# OSO-MISC-21-018_Temperature_Board.net
KiCad netlist of a schematic drawn in EAGLE
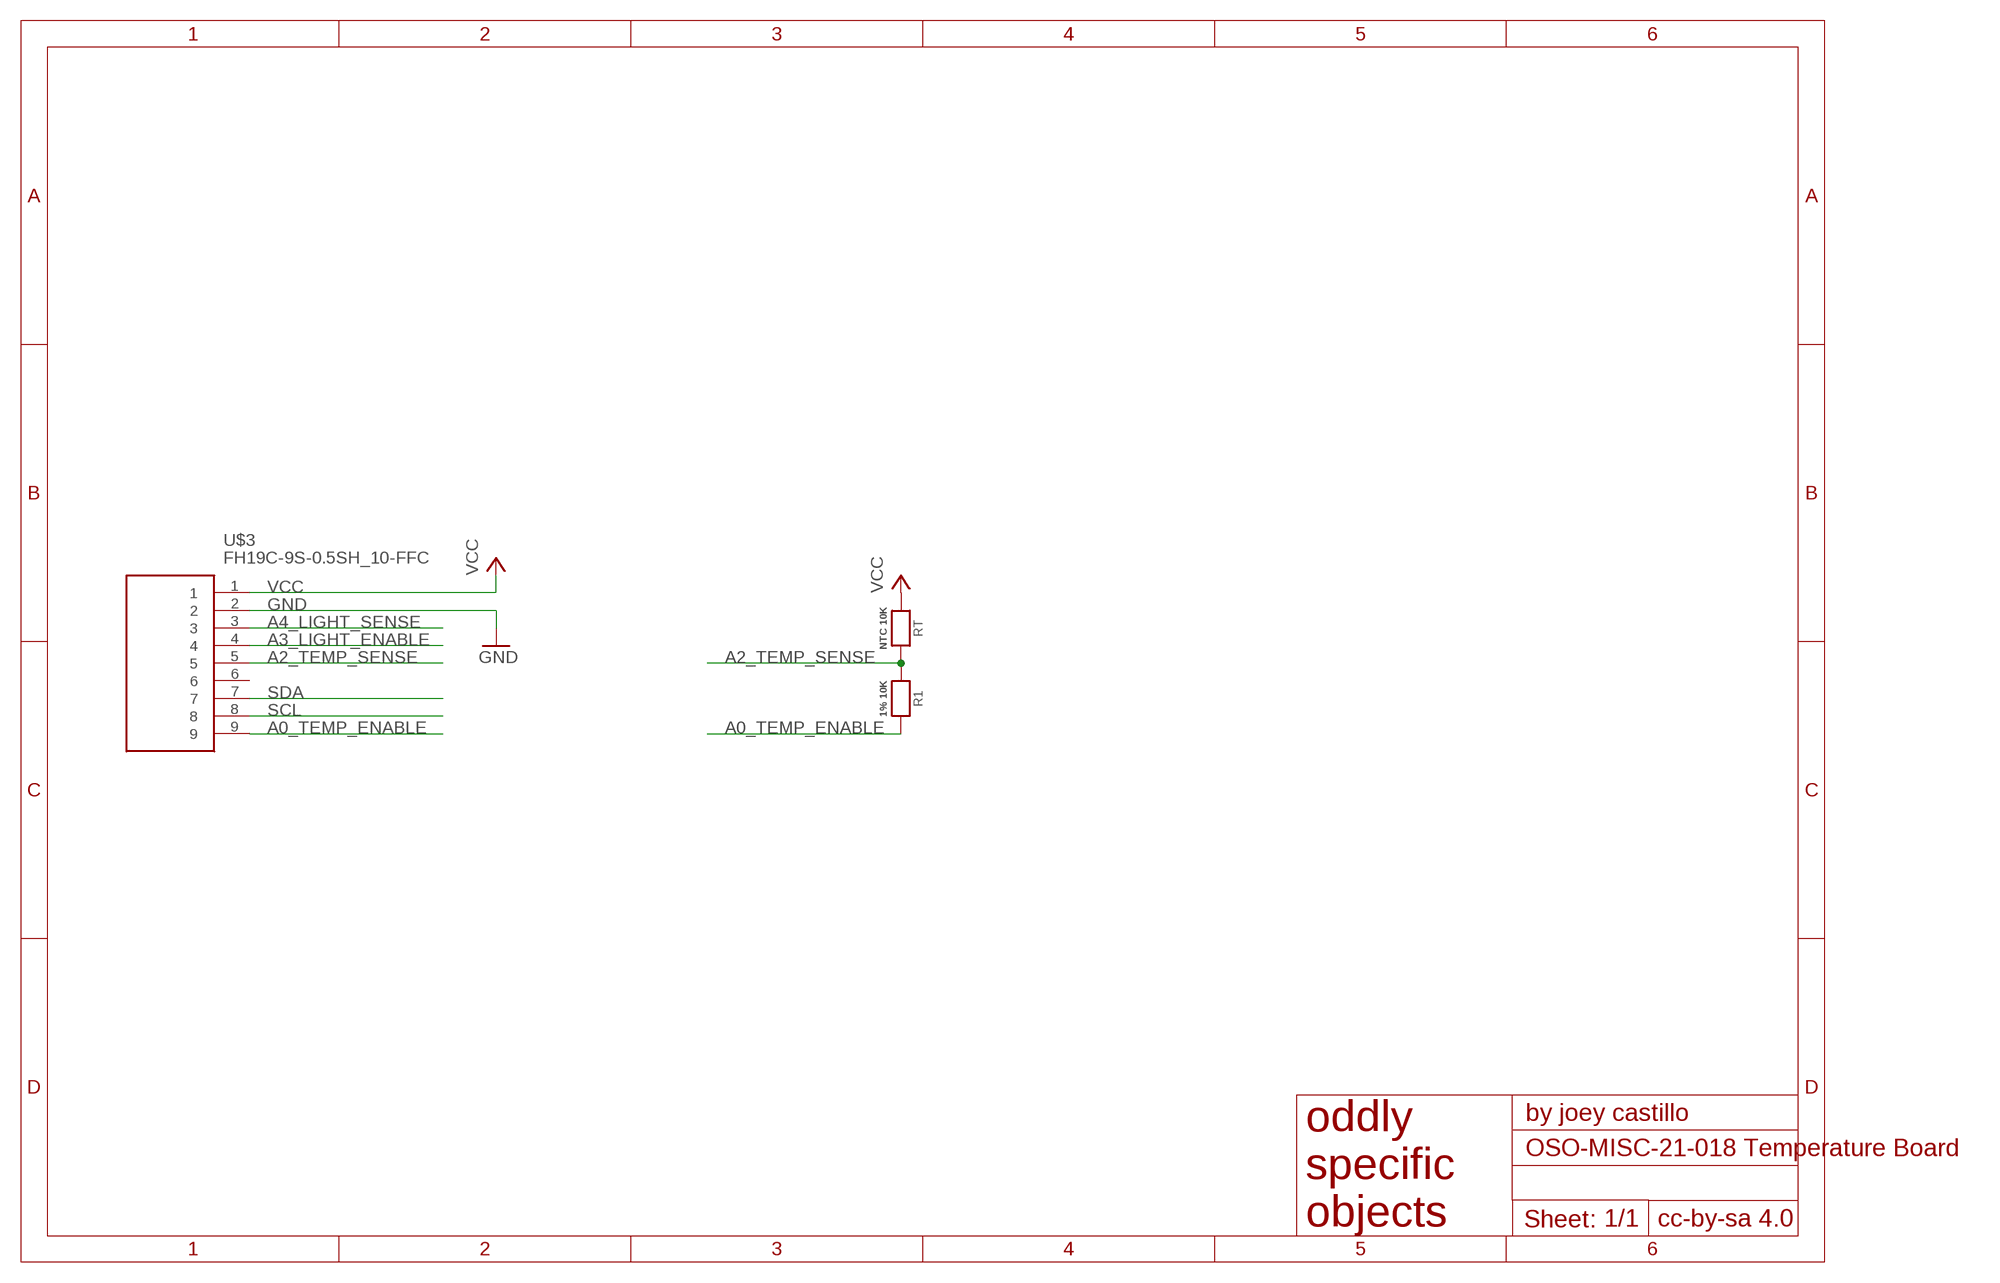
[diagram p0: schematic, sheet 1]

(export (version "E")
  (design (tool "Eeschema 10.0.6"))
  (components
    (comp (ref "R1")
      (value "1% 10K")
      (footprint "eagle-import:_0603MP")
      (libsource (lib "eagle-import") (part "RESISTOR_0603MP"))
    )
    (comp (ref "RT")
      (value "NTC 10K")
      (footprint "eagle-import:_0603")
      (libsource (lib "eagle-import") (part "RESISTOR_0603"))
    )
    (comp (ref "U$3")
      (value "FH19C-9S-0.5SH_10-FFC")
      (footprint "eagle-import:FH19C9S05SH10-FFC")
      (libsource (lib "eagle-import") (part "FH19C-9S-0.5SH_10-FFC"))
    )
  )
  (nets
    (net (code "1") (name "/A0_TEMP_ENABLE") (class "Default")
      (node (ref "R1") (pin "2") (pinfunction "2_2") (pintype "passive"))
      (node (ref "U$3") (pin "9") (pinfunction "9_9") (pintype "bidirectional"))
    )
    (net (code "2") (name "/A2_TEMP_SENSE") (class "Default")
      (node (ref "R1") (pin "1") (pinfunction "1_1") (pintype "passive"))
      (node (ref "RT") (pin "2") (pinfunction "2_2") (pintype "passive"))
      (node (ref "U$3") (pin "5") (pinfunction "5_5") (pintype "bidirectional"))
    )
    (net (code "3") (name "/A3_LIGHT_ENABLE") (class "Default")
      (node (ref "U$3") (pin "4") (pinfunction "4_4") (pintype "bidirectional"))
    )
    (net (code "4") (name "/A4_LIGHT_SENSE") (class "Default")
      (node (ref "U$3") (pin "3") (pinfunction "3_3") (pintype "bidirectional"))
    )
    (net (code "5") (name "/SCL") (class "Default")
      (node (ref "U$3") (pin "8") (pinfunction "8_8") (pintype "bidirectional"))
    )
    (net (code "6") (name "/SDA") (class "Default")
      (node (ref "U$3") (pin "7") (pinfunction "7_7") (pintype "bidirectional"))
    )
    (net (code "7") (name "GND") (class "Default")
      (node (ref "U$3") (pin "2") (pinfunction "2_2") (pintype "bidirectional"))
    )
    (net (code "8") (name "VCC") (class "Default")
      (node (ref "RT") (pin "1") (pinfunction "1_1") (pintype "passive"))
      (node (ref "U$3") (pin "1") (pinfunction "1_1") (pintype "bidirectional"))
    )
    (net (code "9") (name "unconnected-(U$3-Pad6)") (class "Default")
      (node (ref "U$3") (pin "6") (pinfunction "6_6") (pintype "bidirectional"))
    )
  )
)
